# Misc.net
KiCad netlist of a schematic drawn in Altium Designer
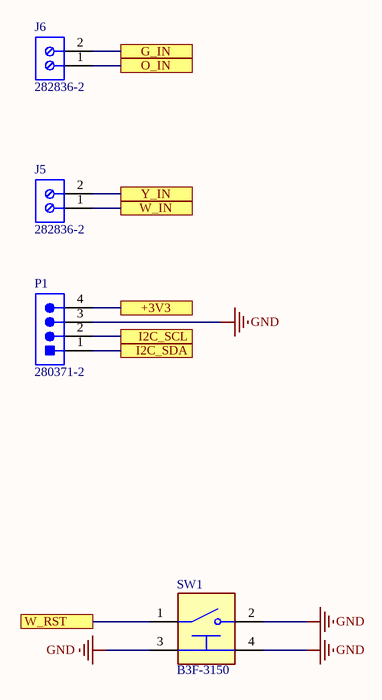
[diagram p0: Misc.SchDoc]

(export (version "E")
  (design (tool "Eeschema 10.0.6"))
  (components
    (comp (ref "J5")
      (value "282836-2")
      (footprint "TECO-282836-2_V")
      (description "Female Header, Pitch 5 mm, 1 x 2 Position, Height 10 mm, Tail Length 3.5 mm, Rohs, Bulk")
      (fields (field (name "VOLTAGE") "300V") (field (name "MANUFACTURER") "TE Connectivity"))
      (libsource (lib "Altium Content Vault") (part "CN-1P-F-TB2"))
    )
    (comp (ref "J6")
      (value "282836-2")
      (footprint "TECO-282836-2_V")
      (description "Female Header, Pitch 5 mm, 1 x 2 Position, Height 10 mm, Tail Length 3.5 mm, Rohs, Bulk")
      (fields (field (name "VOLTAGE") "300V") (field (name "MANUFACTURER") "TE Connectivity"))
      (libsource (lib "Altium Content Vault") (part "CN-1P-F-TB2"))
    )
    (comp (ref "P1")
      (value "280371-2")
      (footprint "TECO-280371-2_V")
      (fields (field (name "MANUFACTURER") "TE Connectivity"))
      (libsource (lib "Altium Content Vault") (part "CN-1P-M-R4"))
    )
    (comp (ref "SW1")
      (value "B3F-3150")
      (footprint "FP-B3F-3150-MFG")
      (description "Tactile Switch SPST-NO Side Actuated Through Hole, Right Angle")
      (fields (field (name "OCTOPART") "https://octopart.com/b3f-3150-omron-49234"))
      (libsource (lib "Altium Content Vault") (part "233cb25b8eba039064bc1ca6c1965ae"))
    )
  )
  (nets
    (net (code "1") (name "/+3V3") (class "Default")
      (node (ref "P1") (pin "4") (pinfunction "4_4") (pintype "passive"))
    )
    (net (code "2") (name "/G_IN") (class "Default")
      (node (ref "J6") (pin "2") (pinfunction "2_2") (pintype "passive"))
    )
    (net (code "3") (name "/I2C_SCL") (class "Default")
      (node (ref "P1") (pin "2") (pinfunction "2_2") (pintype "passive"))
    )
    (net (code "4") (name "/I2C_SDA") (class "Default")
      (node (ref "P1") (pin "1") (pinfunction "1_1") (pintype "passive"))
    )
    (net (code "5") (name "/O_IN") (class "Default")
      (node (ref "J6") (pin "1") (pinfunction "1_1") (pintype "passive"))
    )
    (net (code "6") (name "/W_IN") (class "Default")
      (node (ref "J5") (pin "1") (pinfunction "1_1") (pintype "passive"))
    )
    (net (code "7") (name "/W_RST") (class "Default")
      (node (ref "SW1") (pin "1") (pinfunction "1_1") (pintype "passive"))
    )
    (net (code "8") (name "/Y_IN") (class "Default")
      (node (ref "J5") (pin "2") (pinfunction "2_2") (pintype "passive"))
    )
    (net (code "9") (name "GND") (class "Default")
      (node (ref "P1") (pin "3") (pinfunction "3_3") (pintype "passive"))
      (node (ref "SW1") (pin "2") (pinfunction "2_2") (pintype "passive"))
      (node (ref "SW1") (pin "3") (pinfunction "MNT_1_3") (pintype "passive"))
      (node (ref "SW1") (pin "4") (pinfunction "MNT_2_4") (pintype "passive"))
    )
  )
)
